# AirPi2_Power.net
KiCad netlist of a schematic drawn in Altium Designer
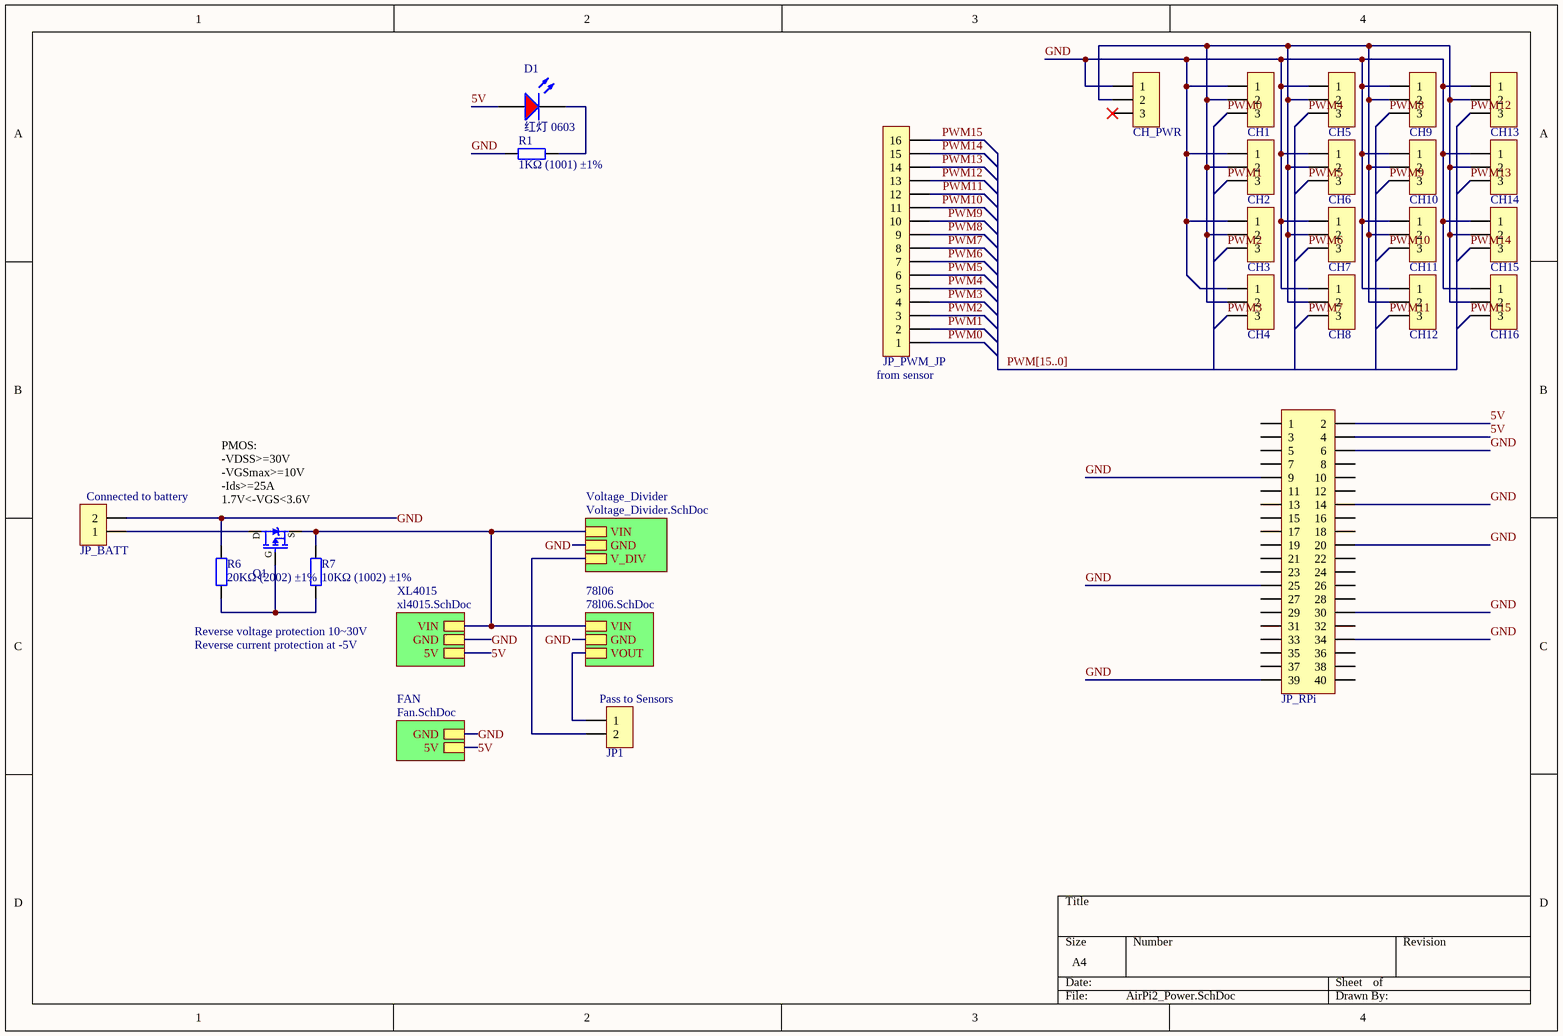
[diagram p0: AirPi2_Power.SchDoc]

(export (version "E")
  (design (tool "Eeschema 10.0.6"))
  (components
    (comp (ref "CH1")
      (value "HDR-1X3")
      (footprint "HDR2.54-LI-3P")
      (description "3P接插件")
      (fields (field (name "版权归属") "源创客"))
      (libsource (lib "4.6   - 接插件-脚距2.54") (part "Header 3"))
    )
    (comp (ref "CH2")
      (value "HDR-1X3")
      (footprint "HDR2.54-LI-3P")
      (description "3P接插件")
      (fields (field (name "版权归属") "源创客"))
      (libsource (lib "4.6   - 接插件-脚距2.54") (part "Header 3"))
    )
    (comp (ref "CH3")
      (value "HDR-1X3")
      (footprint "HDR2.54-LI-3P")
      (description "3P接插件")
      (fields (field (name "版权归属") "源创客"))
      (libsource (lib "4.6   - 接插件-脚距2.54") (part "Header 3"))
    )
    (comp (ref "CH4")
      (value "HDR-1X3")
      (footprint "HDR2.54-LI-3P")
      (description "3P接插件")
      (fields (field (name "版权归属") "源创客"))
      (libsource (lib "4.6   - 接插件-脚距2.54") (part "Header 3"))
    )
    (comp (ref "CH5")
      (value "HDR-1X3")
      (footprint "HDR2.54-LI-3P")
      (description "3P接插件")
      (fields (field (name "版权归属") "源创客"))
      (libsource (lib "4.6   - 接插件-脚距2.54") (part "Header 3"))
    )
    (comp (ref "CH6")
      (value "HDR-1X3")
      (footprint "HDR2.54-LI-3P")
      (description "3P接插件")
      (fields (field (name "版权归属") "源创客"))
      (libsource (lib "4.6   - 接插件-脚距2.54") (part "Header 3"))
    )
    (comp (ref "CH7")
      (value "HDR-1X3")
      (footprint "HDR2.54-LI-3P")
      (description "3P接插件")
      (fields (field (name "版权归属") "源创客"))
      (libsource (lib "4.6   - 接插件-脚距2.54") (part "Header 3"))
    )
    (comp (ref "CH8")
      (value "HDR-1X3")
      (footprint "HDR2.54-LI-3P")
      (description "3P接插件")
      (fields (field (name "版权归属") "源创客"))
      (libsource (lib "4.6   - 接插件-脚距2.54") (part "Header 3"))
    )
    (comp (ref "CH9")
      (value "HDR-1X3")
      (footprint "HDR2.54-LI-3P")
      (description "3P接插件")
      (fields (field (name "版权归属") "源创客"))
      (libsource (lib "4.6   - 接插件-脚距2.54") (part "Header 3"))
    )
    (comp (ref "CH10")
      (value "HDR-1X3")
      (footprint "HDR2.54-LI-3P")
      (description "3P接插件")
      (fields (field (name "版权归属") "源创客"))
      (libsource (lib "4.6   - 接插件-脚距2.54") (part "Header 3"))
    )
    (comp (ref "CH11")
      (value "HDR-1X3")
      (footprint "HDR2.54-LI-3P")
      (description "3P接插件")
      (fields (field (name "版权归属") "源创客"))
      (libsource (lib "4.6   - 接插件-脚距2.54") (part "Header 3"))
    )
    (comp (ref "CH12")
      (value "HDR-1X3")
      (footprint "HDR2.54-LI-3P")
      (description "3P接插件")
      (fields (field (name "版权归属") "源创客"))
      (libsource (lib "4.6   - 接插件-脚距2.54") (part "Header 3"))
    )
    (comp (ref "CH13")
      (value "HDR-1X3")
      (footprint "HDR2.54-LI-3P")
      (description "3P接插件")
      (fields (field (name "版权归属") "源创客"))
      (libsource (lib "4.6   - 接插件-脚距2.54") (part "Header 3"))
    )
    (comp (ref "CH14")
      (value "HDR-1X3")
      (footprint "HDR2.54-LI-3P")
      (description "3P接插件")
      (fields (field (name "版权归属") "源创客"))
      (libsource (lib "4.6   - 接插件-脚距2.54") (part "Header 3"))
    )
    (comp (ref "CH15")
      (value "HDR-1X3")
      (footprint "HDR2.54-LI-3P")
      (description "3P接插件")
      (fields (field (name "版权归属") "源创客"))
      (libsource (lib "4.6   - 接插件-脚距2.54") (part "Header 3"))
    )
    (comp (ref "CH16")
      (value "HDR-1X3")
      (footprint "HDR2.54-LI-3P")
      (description "3P接插件")
      (fields (field (name "版权归属") "源创客"))
      (libsource (lib "4.6   - 接插件-脚距2.54") (part "Header 3"))
    )
    (comp (ref "CH_PWR")
      (value "HDR-1X3")
      (footprint "HDR2.54-LI-3P")
      (description "3P接插件")
      (fields (field (name "版权归属") "源创客"))
      (libsource (lib "4.6   - 接插件-脚距2.54") (part "Header 3"))
    )
    (comp (ref "D1")
      (value "红灯 0603")
      (footprint "0603_LED_S1")
      (description "发光二极管")
      (libsource (lib "Miscellaneous Devices LC") (part "0603 红灯"))
    )
    (comp (ref "JP1")
      (value "HDR-1X2")
      (footprint "HDR2.54-M-LI-2P")
      (description "2P接插件")
      (fields (field (name "版权归属") "源创客"))
      (libsource (lib "4.5   - 接插件-脚距2.54") (part "Header 2"))
    )
    (comp (ref "JP_BATT")
      (value "HDR-1X2")
      (footprint "XH2.54-WI-2P")
      (description "2P接插件")
      (fields (field (name "版权归属") "源创客"))
      (libsource (lib "4.6   - 接插件-脚距2.54") (part "Header 2"))
    )
    (comp (ref "JP_PWM_JP")
      (value "HDR-1X16")
      (footprint "HDR2.54-M-LI-16P")
      (description "16P接插件")
      (fields (field (name "版权归属") "源创客"))
      (libsource (lib "4.5   - 接插件-脚距2.54") (part "Header 16"))
    )
    (comp (ref "JP_RPi")
      (value "Header 2X11")
      (footprint "HDR2.54-LI-2x20P")
      (description "20*2P接插件")
      (fields (field (name "版权归属") "源创客"))
      (libsource (lib "4.5   - 接插件-脚距2.54") (part "Header 20X2"))
    )
    (comp (ref "Q1")
      (value "D15P05")
      (footprint "TO252")
      (description "P沟道 50V/15A")
      (fields (field (name "版权归属") "源创客"))
      (libsource (lib "6.1   - 场效应管-可控硅") (part "D15P05"))
    )
    (comp (ref "R1")
      (value "1KΩ (1001) ±1%")
      (footprint "0805_R")
      (description "贴片电阻")
      (libsource (lib "Miscellaneous Devices LC") (part "0805 1KΩ (1001) 1%"))
    )
    (comp (ref "R6")
      (value "20KΩ (2002) ±1%")
      (footprint "0805_R")
      (description "贴片电阻")
      (libsource (lib "Miscellaneous Devices LC") (part "0805 20KΩ (2002) 1%"))
    )
    (comp (ref "R7")
      (value "10KΩ (1002) ±1%")
      (footprint "0805_R")
      (description "贴片电阻")
      (libsource (lib "Miscellaneous Devices LC") (part "0805 10KΩ (1002) 1%"))
    )
  )
  (nets
    (net (code "1") (name "/5V") (class "Default")
      (node (ref "D1") (pin "A") (pinfunction "A_A") (pintype "passive"))
      (node (ref "JP_RPi") (pin "2") (pinfunction "2_2") (pintype "passive"))
      (node (ref "JP_RPi") (pin "4") (pinfunction "4_4") (pintype "passive"))
    )
    (net (code "2") (name "/GND") (class "Default")
      (node (ref "CH1") (pin "1") (pinfunction "1_1") (pintype "passive"))
      (node (ref "CH10") (pin "1") (pinfunction "1_1") (pintype "passive"))
      (node (ref "CH11") (pin "1") (pinfunction "1_1") (pintype "passive"))
      (node (ref "CH12") (pin "1") (pinfunction "1_1") (pintype "passive"))
      (node (ref "CH13") (pin "1") (pinfunction "1_1") (pintype "passive"))
      (node (ref "CH14") (pin "1") (pinfunction "1_1") (pintype "passive"))
      (node (ref "CH15") (pin "1") (pinfunction "1_1") (pintype "passive"))
      (node (ref "CH16") (pin "1") (pinfunction "1_1") (pintype "passive"))
      (node (ref "CH2") (pin "1") (pinfunction "1_1") (pintype "passive"))
      (node (ref "CH3") (pin "1") (pinfunction "1_1") (pintype "passive"))
      (node (ref "CH4") (pin "1") (pinfunction "1_1") (pintype "passive"))
      (node (ref "CH5") (pin "1") (pinfunction "1_1") (pintype "passive"))
      (node (ref "CH6") (pin "1") (pinfunction "1_1") (pintype "passive"))
      (node (ref "CH7") (pin "1") (pinfunction "1_1") (pintype "passive"))
      (node (ref "CH8") (pin "1") (pinfunction "1_1") (pintype "passive"))
      (node (ref "CH9") (pin "1") (pinfunction "1_1") (pintype "passive"))
      (node (ref "CH_PWR") (pin "1") (pinfunction "1_1") (pintype "passive"))
      (node (ref "JP_BATT") (pin "2") (pinfunction "2_2") (pintype "power_in"))
      (node (ref "JP_RPi") (pin "14") (pinfunction "14_14") (pintype "passive"))
      (node (ref "JP_RPi") (pin "20") (pinfunction "20_20") (pintype "passive"))
      (node (ref "JP_RPi") (pin "25") (pinfunction "25_25") (pintype "passive"))
      (node (ref "JP_RPi") (pin "30") (pinfunction "30_30") (pintype "passive"))
      (node (ref "JP_RPi") (pin "34") (pinfunction "34_34") (pintype "passive"))
      (node (ref "JP_RPi") (pin "39") (pinfunction "39_39") (pintype "passive"))
      (node (ref "JP_RPi") (pin "6") (pinfunction "6_6") (pintype "passive"))
      (node (ref "JP_RPi") (pin "9") (pinfunction "9_9") (pintype "passive"))
      (node (ref "R1") (pin "1") (pinfunction "1_1") (pintype "passive"))
      (node (ref "R6") (pin "2") (pinfunction "2_2") (pintype "passive"))
    )
    (net (code "3") (name "/PWM0") (class "Default")
      (node (ref "CH1") (pin "3") (pinfunction "3_3") (pintype "passive"))
      (node (ref "JP_PWM_JP") (pin "1") (pinfunction "1_1") (pintype "passive"))
    )
    (net (code "4") (name "/PWM1") (class "Default")
      (node (ref "CH2") (pin "3") (pinfunction "3_3") (pintype "passive"))
      (node (ref "JP_PWM_JP") (pin "2") (pinfunction "2_2") (pintype "passive"))
    )
    (net (code "5") (name "/PWM2") (class "Default")
      (node (ref "CH3") (pin "3") (pinfunction "3_3") (pintype "passive"))
      (node (ref "JP_PWM_JP") (pin "3") (pinfunction "3_3") (pintype "passive"))
    )
    (net (code "6") (name "/PWM3") (class "Default")
      (node (ref "CH4") (pin "3") (pinfunction "3_3") (pintype "passive"))
      (node (ref "JP_PWM_JP") (pin "4") (pinfunction "4_4") (pintype "passive"))
    )
    (net (code "7") (name "/PWM4") (class "Default")
      (node (ref "CH5") (pin "3") (pinfunction "3_3") (pintype "passive"))
      (node (ref "JP_PWM_JP") (pin "5") (pinfunction "5_5") (pintype "passive"))
    )
    (net (code "8") (name "/PWM5") (class "Default")
      (node (ref "CH6") (pin "3") (pinfunction "3_3") (pintype "passive"))
      (node (ref "JP_PWM_JP") (pin "6") (pinfunction "6_6") (pintype "passive"))
    )
    (net (code "9") (name "/PWM6") (class "Default")
      (node (ref "CH7") (pin "3") (pinfunction "3_3") (pintype "passive"))
      (node (ref "JP_PWM_JP") (pin "7") (pinfunction "7_7") (pintype "passive"))
    )
    (net (code "10") (name "/PWM7") (class "Default")
      (node (ref "CH8") (pin "3") (pinfunction "3_3") (pintype "passive"))
      (node (ref "JP_PWM_JP") (pin "8") (pinfunction "8_8") (pintype "passive"))
    )
    (net (code "11") (name "/PWM8") (class "Default")
      (node (ref "CH9") (pin "3") (pinfunction "3_3") (pintype "passive"))
      (node (ref "JP_PWM_JP") (pin "9") (pinfunction "9_9") (pintype "passive"))
    )
    (net (code "12") (name "/PWM9") (class "Default")
      (node (ref "CH10") (pin "3") (pinfunction "3_3") (pintype "passive"))
      (node (ref "JP_PWM_JP") (pin "10") (pinfunction "10_10") (pintype "passive"))
    )
    (net (code "13") (name "/PWM10") (class "Default")
      (node (ref "CH11") (pin "3") (pinfunction "3_3") (pintype "passive"))
      (node (ref "JP_PWM_JP") (pin "11") (pinfunction "11_11") (pintype "passive"))
    )
    (net (code "14") (name "/PWM11") (class "Default")
      (node (ref "CH12") (pin "3") (pinfunction "3_3") (pintype "passive"))
      (node (ref "JP_PWM_JP") (pin "12") (pinfunction "12_12") (pintype "passive"))
    )
    (net (code "15") (name "/PWM12") (class "Default")
      (node (ref "CH13") (pin "3") (pinfunction "3_3") (pintype "passive"))
      (node (ref "JP_PWM_JP") (pin "13") (pinfunction "13_13") (pintype "passive"))
    )
    (net (code "16") (name "/PWM13") (class "Default")
      (node (ref "CH14") (pin "3") (pinfunction "3_3") (pintype "passive"))
      (node (ref "JP_PWM_JP") (pin "14") (pinfunction "14_14") (pintype "passive"))
    )
    (net (code "17") (name "/PWM14") (class "Default")
      (node (ref "CH15") (pin "3") (pinfunction "3_3") (pintype "passive"))
      (node (ref "JP_PWM_JP") (pin "15") (pinfunction "15_15") (pintype "passive"))
    )
    (net (code "18") (name "/PWM15") (class "Default")
      (node (ref "CH16") (pin "3") (pinfunction "3_3") (pintype "passive"))
      (node (ref "JP_PWM_JP") (pin "16") (pinfunction "16_16") (pintype "passive"))
    )
    (net (code "20") (name "/VIN") (class "Default")
      (node (ref "Q1") (pin "3") (pinfunction "D_3") (pintype "passive"))
      (node (ref "R7") (pin "2") (pinfunction "2_2") (pintype "passive"))
    )
    (net (code "21") (name "/VOUT") (class "Default")
      (node (ref "JP1") (pin "1") (pinfunction "1_1") (pintype "passive"))
    )
    (net (code "22") (name "/V_DIV") (class "Default")
      (node (ref "JP1") (pin "2") (pinfunction "2_2") (pintype "passive"))
    )
    (net (code "23") (name "Net-(CH1-Pad2)") (class "Default")
      (node (ref "CH1") (pin "2") (pinfunction "2_2") (pintype "passive"))
      (node (ref "CH10") (pin "2") (pinfunction "2_2") (pintype "passive"))
      (node (ref "CH11") (pin "2") (pinfunction "2_2") (pintype "passive"))
      (node (ref "CH12") (pin "2") (pinfunction "2_2") (pintype "passive"))
      (node (ref "CH13") (pin "2") (pinfunction "2_2") (pintype "passive"))
      (node (ref "CH14") (pin "2") (pinfunction "2_2") (pintype "passive"))
      (node (ref "CH15") (pin "2") (pinfunction "2_2") (pintype "passive"))
      (node (ref "CH16") (pin "2") (pinfunction "2_2") (pintype "passive"))
      (node (ref "CH2") (pin "2") (pinfunction "2_2") (pintype "passive"))
      (node (ref "CH3") (pin "2") (pinfunction "2_2") (pintype "passive"))
      (node (ref "CH4") (pin "2") (pinfunction "2_2") (pintype "passive"))
      (node (ref "CH5") (pin "2") (pinfunction "2_2") (pintype "passive"))
      (node (ref "CH6") (pin "2") (pinfunction "2_2") (pintype "passive"))
      (node (ref "CH7") (pin "2") (pinfunction "2_2") (pintype "passive"))
      (node (ref "CH8") (pin "2") (pinfunction "2_2") (pintype "passive"))
      (node (ref "CH9") (pin "2") (pinfunction "2_2") (pintype "passive"))
      (node (ref "CH_PWR") (pin "2") (pinfunction "2_2") (pintype "passive"))
    )
    (net (code "24") (name "Net-(D1-PadK)") (class "Default")
      (node (ref "D1") (pin "K") (pinfunction "K_K") (pintype "passive"))
      (node (ref "R1") (pin "2") (pinfunction "2_2") (pintype "passive"))
    )
    (net (code "25") (name "Net-(Q1-G)") (class "Default")
      (node (ref "Q1") (pin "1") (pinfunction "G_1") (pintype "passive"))
      (node (ref "R6") (pin "1") (pinfunction "1_1") (pintype "passive"))
      (node (ref "R7") (pin "1") (pinfunction "1_1") (pintype "passive"))
    )
    (net (code "26") (name "Net-(Q1-S)") (class "Default")
      (node (ref "JP_BATT") (pin "1") (pinfunction "1_1") (pintype "power_in"))
      (node (ref "Q1") (pin "2") (pinfunction "S_2") (pintype "passive"))
    )
    (net (code "27") (name "unconnected-(CH_PWR-Pad3)") (class "Default")
      (node (ref "CH_PWR") (pin "3") (pinfunction "3_3") (pintype "passive+no_connect"))
    )
    (net (code "28") (name "unconnected-(JP_RPi-Pad1)") (class "Default")
      (node (ref "JP_RPi") (pin "1") (pinfunction "1_1") (pintype "passive"))
    )
    (net (code "29") (name "unconnected-(JP_RPi-Pad3)") (class "Default")
      (node (ref "JP_RPi") (pin "3") (pinfunction "3_3") (pintype "passive"))
    )
    (net (code "30") (name "unconnected-(JP_RPi-Pad5)") (class "Default")
      (node (ref "JP_RPi") (pin "5") (pinfunction "5_5") (pintype "passive"))
    )
    (net (code "31") (name "unconnected-(JP_RPi-Pad7)") (class "Default")
      (node (ref "JP_RPi") (pin "7") (pinfunction "7_7") (pintype "passive"))
    )
    (net (code "32") (name "unconnected-(JP_RPi-Pad8)") (class "Default")
      (node (ref "JP_RPi") (pin "8") (pinfunction "8_8") (pintype "passive"))
    )
    (net (code "33") (name "unconnected-(JP_RPi-Pad10)") (class "Default")
      (node (ref "JP_RPi") (pin "10") (pinfunction "10_10") (pintype "passive"))
    )
    (net (code "34") (name "unconnected-(JP_RPi-Pad11)") (class "Default")
      (node (ref "JP_RPi") (pin "11") (pinfunction "11_11") (pintype "passive"))
    )
    (net (code "35") (name "unconnected-(JP_RPi-Pad12)") (class "Default")
      (node (ref "JP_RPi") (pin "12") (pinfunction "12_12") (pintype "passive"))
    )
    (net (code "36") (name "unconnected-(JP_RPi-Pad13)") (class "Default")
      (node (ref "JP_RPi") (pin "13") (pinfunction "13_13") (pintype "passive"))
    )
    (net (code "37") (name "unconnected-(JP_RPi-Pad15)") (class "Default")
      (node (ref "JP_RPi") (pin "15") (pinfunction "15_15") (pintype "passive"))
    )
    (net (code "38") (name "unconnected-(JP_RPi-Pad16)") (class "Default")
      (node (ref "JP_RPi") (pin "16") (pinfunction "16_16") (pintype "passive"))
    )
    (net (code "39") (name "unconnected-(JP_RPi-Pad17)") (class "Default")
      (node (ref "JP_RPi") (pin "17") (pinfunction "17_17") (pintype "passive"))
    )
    (net (code "40") (name "unconnected-(JP_RPi-Pad18)") (class "Default")
      (node (ref "JP_RPi") (pin "18") (pinfunction "18_18") (pintype "passive"))
    )
    (net (code "41") (name "unconnected-(JP_RPi-Pad19)") (class "Default")
      (node (ref "JP_RPi") (pin "19") (pinfunction "19_19") (pintype "passive"))
    )
    (net (code "42") (name "unconnected-(JP_RPi-Pad21)") (class "Default")
      (node (ref "JP_RPi") (pin "21") (pinfunction "21_21") (pintype "passive"))
    )
    (net (code "43") (name "unconnected-(JP_RPi-Pad22)") (class "Default")
      (node (ref "JP_RPi") (pin "22") (pinfunction "22_22") (pintype "passive"))
    )
    (net (code "44") (name "unconnected-(JP_RPi-Pad23)") (class "Default")
      (node (ref "JP_RPi") (pin "23") (pinfunction "23_23") (pintype "passive"))
    )
    (net (code "45") (name "unconnected-(JP_RPi-Pad24)") (class "Default")
      (node (ref "JP_RPi") (pin "24") (pinfunction "24_24") (pintype "passive"))
    )
    (net (code "46") (name "unconnected-(JP_RPi-Pad26)") (class "Default")
      (node (ref "JP_RPi") (pin "26") (pinfunction "26_26") (pintype "passive"))
    )
    (net (code "47") (name "unconnected-(JP_RPi-Pad27)") (class "Default")
      (node (ref "JP_RPi") (pin "27") (pinfunction "27_27") (pintype "passive"))
    )
    (net (code "48") (name "unconnected-(JP_RPi-Pad28)") (class "Default")
      (node (ref "JP_RPi") (pin "28") (pinfunction "28_28") (pintype "passive"))
    )
    (net (code "49") (name "unconnected-(JP_RPi-Pad29)") (class "Default")
      (node (ref "JP_RPi") (pin "29") (pinfunction "29_29") (pintype "passive"))
    )
    (net (code "50") (name "unconnected-(JP_RPi-Pad31)") (class "Default")
      (node (ref "JP_RPi") (pin "31") (pinfunction "31_31") (pintype "passive"))
    )
    (net (code "51") (name "unconnected-(JP_RPi-Pad32)") (class "Default")
      (node (ref "JP_RPi") (pin "32") (pinfunction "32_32") (pintype "passive"))
    )
    (net (code "52") (name "unconnected-(JP_RPi-Pad33)") (class "Default")
      (node (ref "JP_RPi") (pin "33") (pinfunction "33_33") (pintype "passive"))
    )
    (net (code "53") (name "unconnected-(JP_RPi-Pad35)") (class "Default")
      (node (ref "JP_RPi") (pin "35") (pinfunction "35_35") (pintype "passive"))
    )
    (net (code "54") (name "unconnected-(JP_RPi-Pad36)") (class "Default")
      (node (ref "JP_RPi") (pin "36") (pinfunction "36_36") (pintype "passive"))
    )
    (net (code "55") (name "unconnected-(JP_RPi-Pad37)") (class "Default")
      (node (ref "JP_RPi") (pin "37") (pinfunction "37_37") (pintype "passive"))
    )
    (net (code "56") (name "unconnected-(JP_RPi-Pad38)") (class "Default")
      (node (ref "JP_RPi") (pin "38") (pinfunction "38_38") (pintype "passive"))
    )
    (net (code "57") (name "unconnected-(JP_RPi-Pad40)") (class "Default")
      (node (ref "JP_RPi") (pin "40") (pinfunction "40_40") (pintype "passive"))
    )
  )
)
